# TempMonADC.net
KiCad netlist of a schematic drawn in Altium Designer
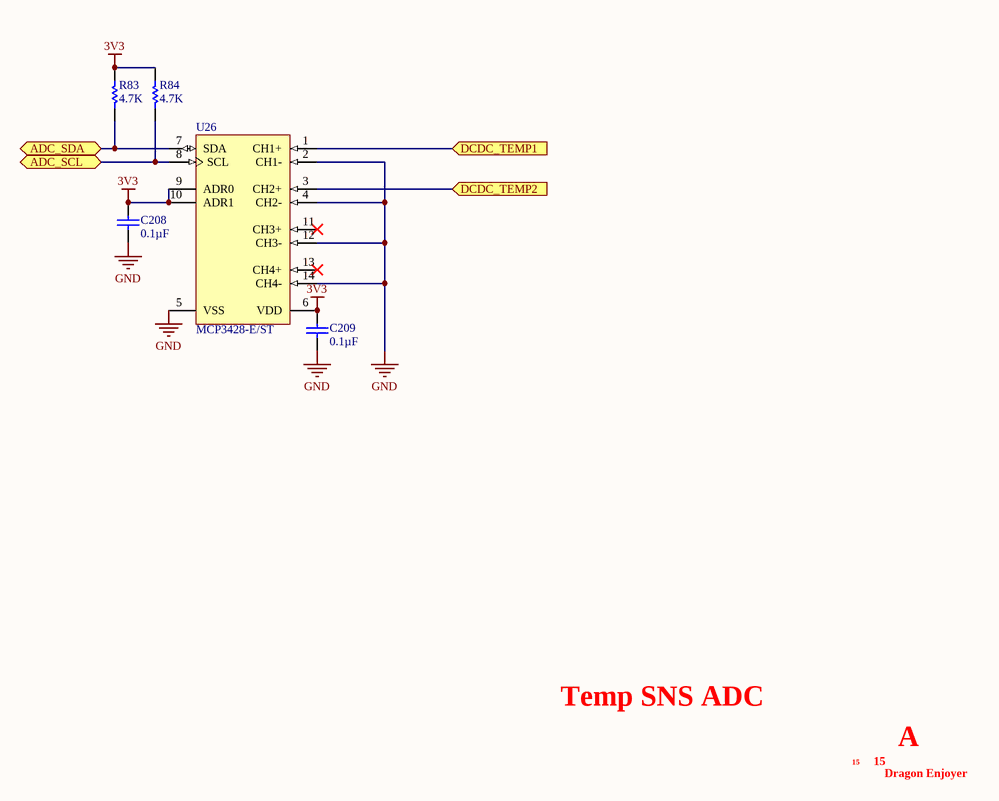
[diagram p0: TempMonADC.SchDoc]

(export (version "E")
  (design (tool "Eeschema 10.0.6"))
  (components
    (comp (ref "C208")
      (value "CC0402ZRY5V8BB104")
      (footprint "CAPC1005X55X25LL05T05")
      (description "Chip Capacitor, 100 nF, -20% to 80%, 25 V, -30 to 85 degC, 0402 (1005 Metric), RoHS, Tape and Reel")
      (fields
        (field (name "TOLERANCE") "-20%,+80%")
        (field (name "CAPACITANCE") "0.1µF")
        (field (name "MANUFACTURER") "Yageo")
      )
      (libsource (lib "Altium Content Vault") (part "CAP-NP-2"))
    )
    (comp (ref "C209")
      (value "CC0402ZRY5V8BB104")
      (footprint "CAPC1005X55X25LL05T05")
      (description "Chip Capacitor, 100 nF, -20% to 80%, 25 V, -30 to 85 degC, 0402 (1005 Metric), RoHS, Tape and Reel")
      (fields
        (field (name "TOLERANCE") "-20%,+80%")
        (field (name "CAPACITANCE") "0.1µF")
        (field (name "MANUFACTURER") "Yageo")
      )
      (libsource (lib "Altium Content Vault") (part "CAP-NP-2"))
    )
    (comp (ref "R83")
      (value "4.7K")
      (footprint "RESC1005X40X25LL05T10")
      (fields (field (name "PART NUMBER") "RC0402JR-074K7L") (field (name "MANUFACTURER") "Yageo / Phycomp"))
      (libsource (lib "Altium Content Vault") (part "RES"))
    )
    (comp (ref "R84")
      (value "4.7K")
      (footprint "RESC1005X40X25LL05T10")
      (fields (field (name "PART NUMBER") "RC0402JR-074K7L") (field (name "MANUFACTURER") "Yageo / Phycomp"))
      (libsource (lib "Altium Content Vault") (part "RES"))
    )
    (comp (ref "U26")
      (value "MCP3428-E/ST")
      (footprint "TSSOP-ST14_L")
      (libsource (lib "Altium Content Vault") (part "CON-ADC-MCP3428-14"))
    )
  )
  (nets
    (net (code "1") (name "/ADC_SCL") (class "Default")
      (node (ref "R84") (pin "2") (pinfunction "2_2") (pintype "passive"))
      (node (ref "U26") (pin "8") (pinfunction "SCL_8") (pintype "input"))
    )
    (net (code "2") (name "/ADC_SDA") (class "Default")
      (node (ref "R83") (pin "2") (pinfunction "2_2") (pintype "passive"))
      (node (ref "U26") (pin "7") (pinfunction "SDA_7") (pintype "bidirectional"))
    )
    (net (code "3") (name "/DCDC_TEMP1") (class "Default")
      (node (ref "U26") (pin "1") (pinfunction "CH1+_1") (pintype "input"))
    )
    (net (code "4") (name "/DCDC_TEMP2") (class "Default")
      (node (ref "U26") (pin "3") (pinfunction "CH2+_3") (pintype "input"))
    )
    (net (code "5") (name "3V3") (class "Default")
      (node (ref "C208") (pin "2") (pinfunction "2_2") (pintype "passive"))
      (node (ref "C209") (pin "2") (pinfunction "2_2") (pintype "passive"))
      (node (ref "R83") (pin "1") (pinfunction "1_1") (pintype "passive"))
      (node (ref "R84") (pin "1") (pinfunction "1_1") (pintype "passive"))
      (node (ref "U26") (pin "10") (pinfunction "ADR1_10") (pintype "passive"))
      (node (ref "U26") (pin "6") (pinfunction "VDD_6") (pintype "power_in"))
      (node (ref "U26") (pin "9") (pinfunction "ADR0_9") (pintype "passive"))
    )
    (net (code "6") (name "GND") (class "Default")
      (node (ref "C208") (pin "1") (pinfunction "1_1") (pintype "passive"))
      (node (ref "C209") (pin "1") (pinfunction "1_1") (pintype "passive"))
      (node (ref "U26") (pin "12") (pinfunction "CH3-_12") (pintype "input"))
      (node (ref "U26") (pin "14") (pinfunction "CH4-_14") (pintype "input"))
      (node (ref "U26") (pin "2") (pinfunction "CH1-_2") (pintype "input"))
      (node (ref "U26") (pin "4") (pinfunction "CH2-_4") (pintype "input"))
      (node (ref "U26") (pin "5") (pinfunction "VSS_5") (pintype "power_in"))
    )
    (net (code "7") (name "unconnected-(U26-CH3+-Pad11)") (class "Default")
      (node (ref "U26") (pin "11") (pinfunction "CH3+_11") (pintype "input+no_connect"))
    )
    (net (code "8") (name "unconnected-(U26-CH4+-Pad13)") (class "Default")
      (node (ref "U26") (pin "13") (pinfunction "CH4+_13") (pintype "input+no_connect"))
    )
  )
)
